# make_etf_great_again.net
KiCad netlist of a schematic drawn in Altium Designer
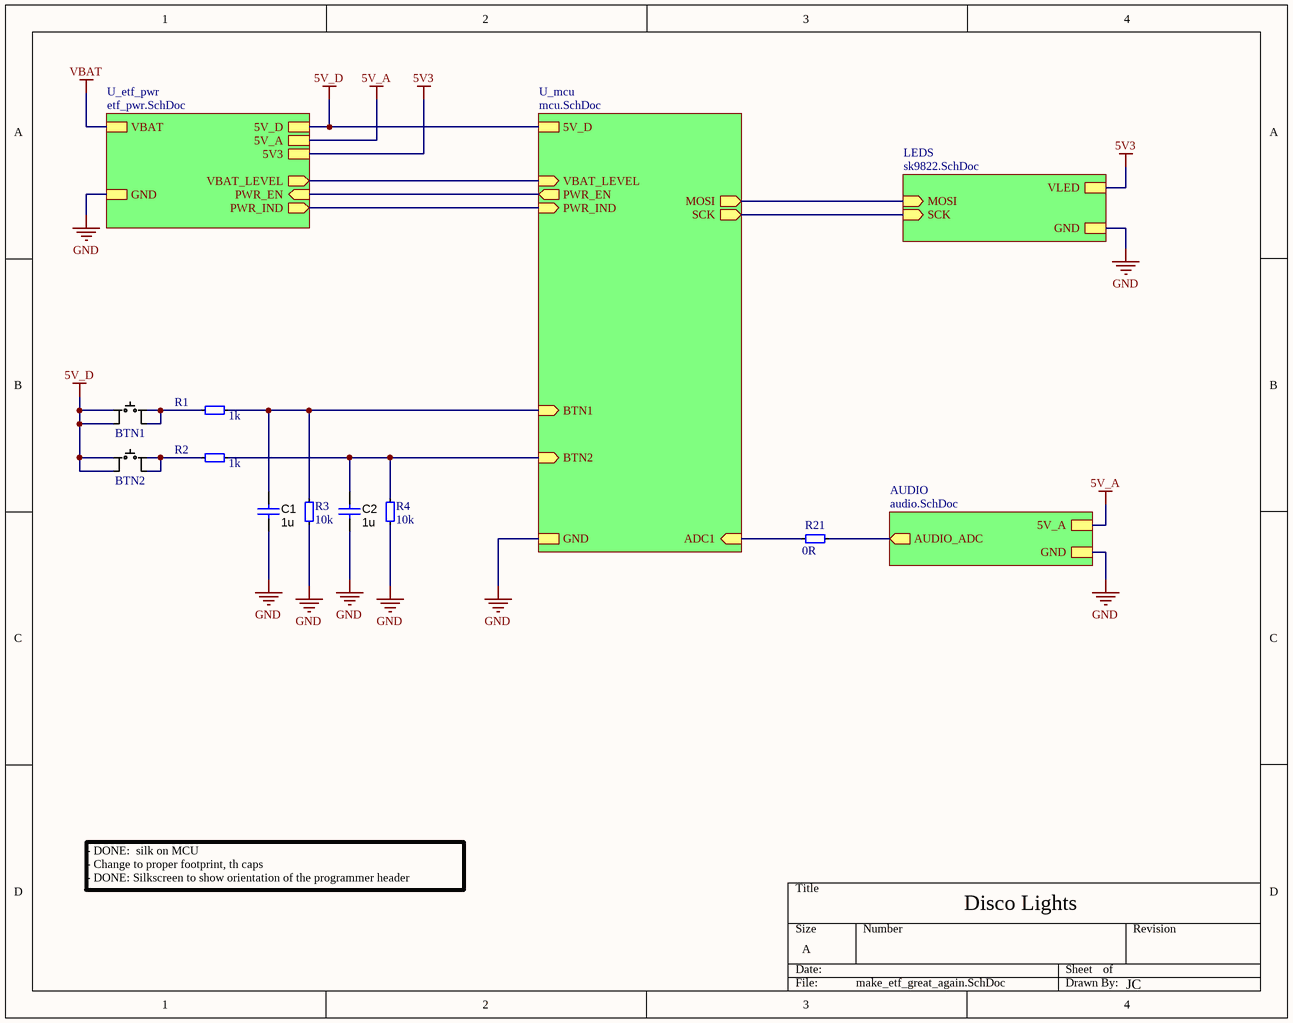
[diagram p0: make_etf_great_again.SchDoc]

(export (version "E")
  (design (tool "Eeschema 10.0.6"))
  (components
    (comp (ref "BTN1")
      (value "Tactile Button")
      (footprint "SW_TS02-66-150-BK-160-LCR-D")
      (description "Tactile Switch Small Low")
      (libsource (lib "urad") (part "TacButton TH"))
    )
    (comp (ref "BTN2")
      (value "Tactile Button")
      (footprint "SW_TS02-66-150-BK-160-LCR-D")
      (description "Tactile Switch Small Low")
      (libsource (lib "urad") (part "TacButton TH"))
    )
    (comp (ref "C1")
      (value "1u")
      (footprint "1206_180")
      (fields
        (field (name "JLCPCB PART #") "C527272")
        (field (name "MANUFACTURER PART NUMBER") "CC1206JKX7R7BB105")
        (field (name "Comment") "CAP, 1206")
      )
      (libsource (lib "urad") (part "CAP, 1206"))
    )
    (comp (ref "C2")
      (value "1u")
      (footprint "1206_180")
      (fields
        (field (name "JLCPCB PART #") "C527272")
        (field (name "MANUFACTURER PART NUMBER") "CC1206JKX7R7BB105")
        (field (name "Comment") "CAP, 1206")
      )
      (libsource (lib "urad") (part "CAP, 1206"))
    )
    (comp (ref "R1")
      (value "1k")
      (footprint "TH")
      (fields (field (name "Comment") "TH, resistor"))
      (libsource (lib "jclib") (part "TH, resistor"))
    )
    (comp (ref "R2")
      (value "1k")
      (footprint "TH")
      (fields (field (name "Comment") "TH, resistor"))
      (libsource (lib "jclib") (part "TH, resistor"))
    )
    (comp (ref "R3")
      (value "10k")
      (footprint "TH")
      (fields (field (name "Comment") "TH, resistor"))
      (libsource (lib "jclib") (part "TH, resistor"))
    )
    (comp (ref "R4")
      (value "10k")
      (footprint "TH")
      (fields (field (name "Comment") "TH, resistor"))
      (libsource (lib "jclib") (part "TH, resistor"))
    )
    (comp (ref "R21")
      (value "0R")
      (footprint "0603")
      (fields
        (field (name "JLCPCB PART #") "C95177")
        (field (name "MANUFACTURER PART NUMBER") "RC0603JR-070RL")
        (field (name "Comment") "0603, resistor")
      )
      (libsource (lib "jclib") (part "0603, resistor"))
    )
  )
  (nets
    (net (code "1") (name "/ADC1") (class "Default")
      (node (ref "R21") (pin "1") (pinfunction "1_1") (pintype "passive"))
    )
    (net (code "2") (name "/AUDIO_ADC") (class "Default")
      (node (ref "R21") (pin "0") (pinfunction "0_0") (pintype "passive"))
    )
    (net (code "3") (name "/BTN1") (class "Default")
      (node (ref "C1") (pin "1") (pinfunction "1_1") (pintype "passive"))
      (node (ref "R1") (pin "2") (pinfunction "2_2") (pintype "passive"))
      (node (ref "R3") (pin "2") (pinfunction "2_2") (pintype "passive"))
    )
    (net (code "4") (name "/BTN2") (class "Default")
      (node (ref "C2") (pin "1") (pinfunction "1_1") (pintype "passive"))
      (node (ref "R2") (pin "2") (pinfunction "2_2") (pintype "passive"))
      (node (ref "R4") (pin "2") (pinfunction "2_2") (pintype "passive"))
    )
    (net (code "12") (name "5V_D") (class "Default")
      (node (ref "BTN1") (pin "3") (pinfunction "3_3") (pintype "passive"))
      (node (ref "BTN1") (pin "4") (pinfunction "4_4") (pintype "passive"))
      (node (ref "BTN2") (pin "3") (pinfunction "3_3") (pintype "passive"))
      (node (ref "BTN2") (pin "4") (pinfunction "4_4") (pintype "passive"))
    )
    (net (code "13") (name "GND") (class "Default")
      (node (ref "C1") (pin "2") (pinfunction "2_2") (pintype "passive"))
      (node (ref "C2") (pin "2") (pinfunction "2_2") (pintype "passive"))
      (node (ref "R3") (pin "1") (pinfunction "1_1") (pintype "passive"))
      (node (ref "R4") (pin "1") (pinfunction "1_1") (pintype "passive"))
    )
    (net (code "14") (name "Net-(BTN1-Pad1)") (class "Default")
      (node (ref "BTN1") (pin "1") (pinfunction "1_1") (pintype "passive"))
      (node (ref "BTN1") (pin "2") (pinfunction "2_2") (pintype "passive"))
      (node (ref "R1") (pin "1") (pinfunction "1_1") (pintype "passive"))
    )
    (net (code "15") (name "Net-(BTN2-Pad1)") (class "Default")
      (node (ref "BTN2") (pin "1") (pinfunction "1_1") (pintype "passive"))
      (node (ref "BTN2") (pin "2") (pinfunction "2_2") (pintype "passive"))
      (node (ref "R2") (pin "1") (pinfunction "1_1") (pintype "passive"))
    )
  )
)
